# version2_PNP.net
KiCad netlist of a schematic drawn in EAGLE
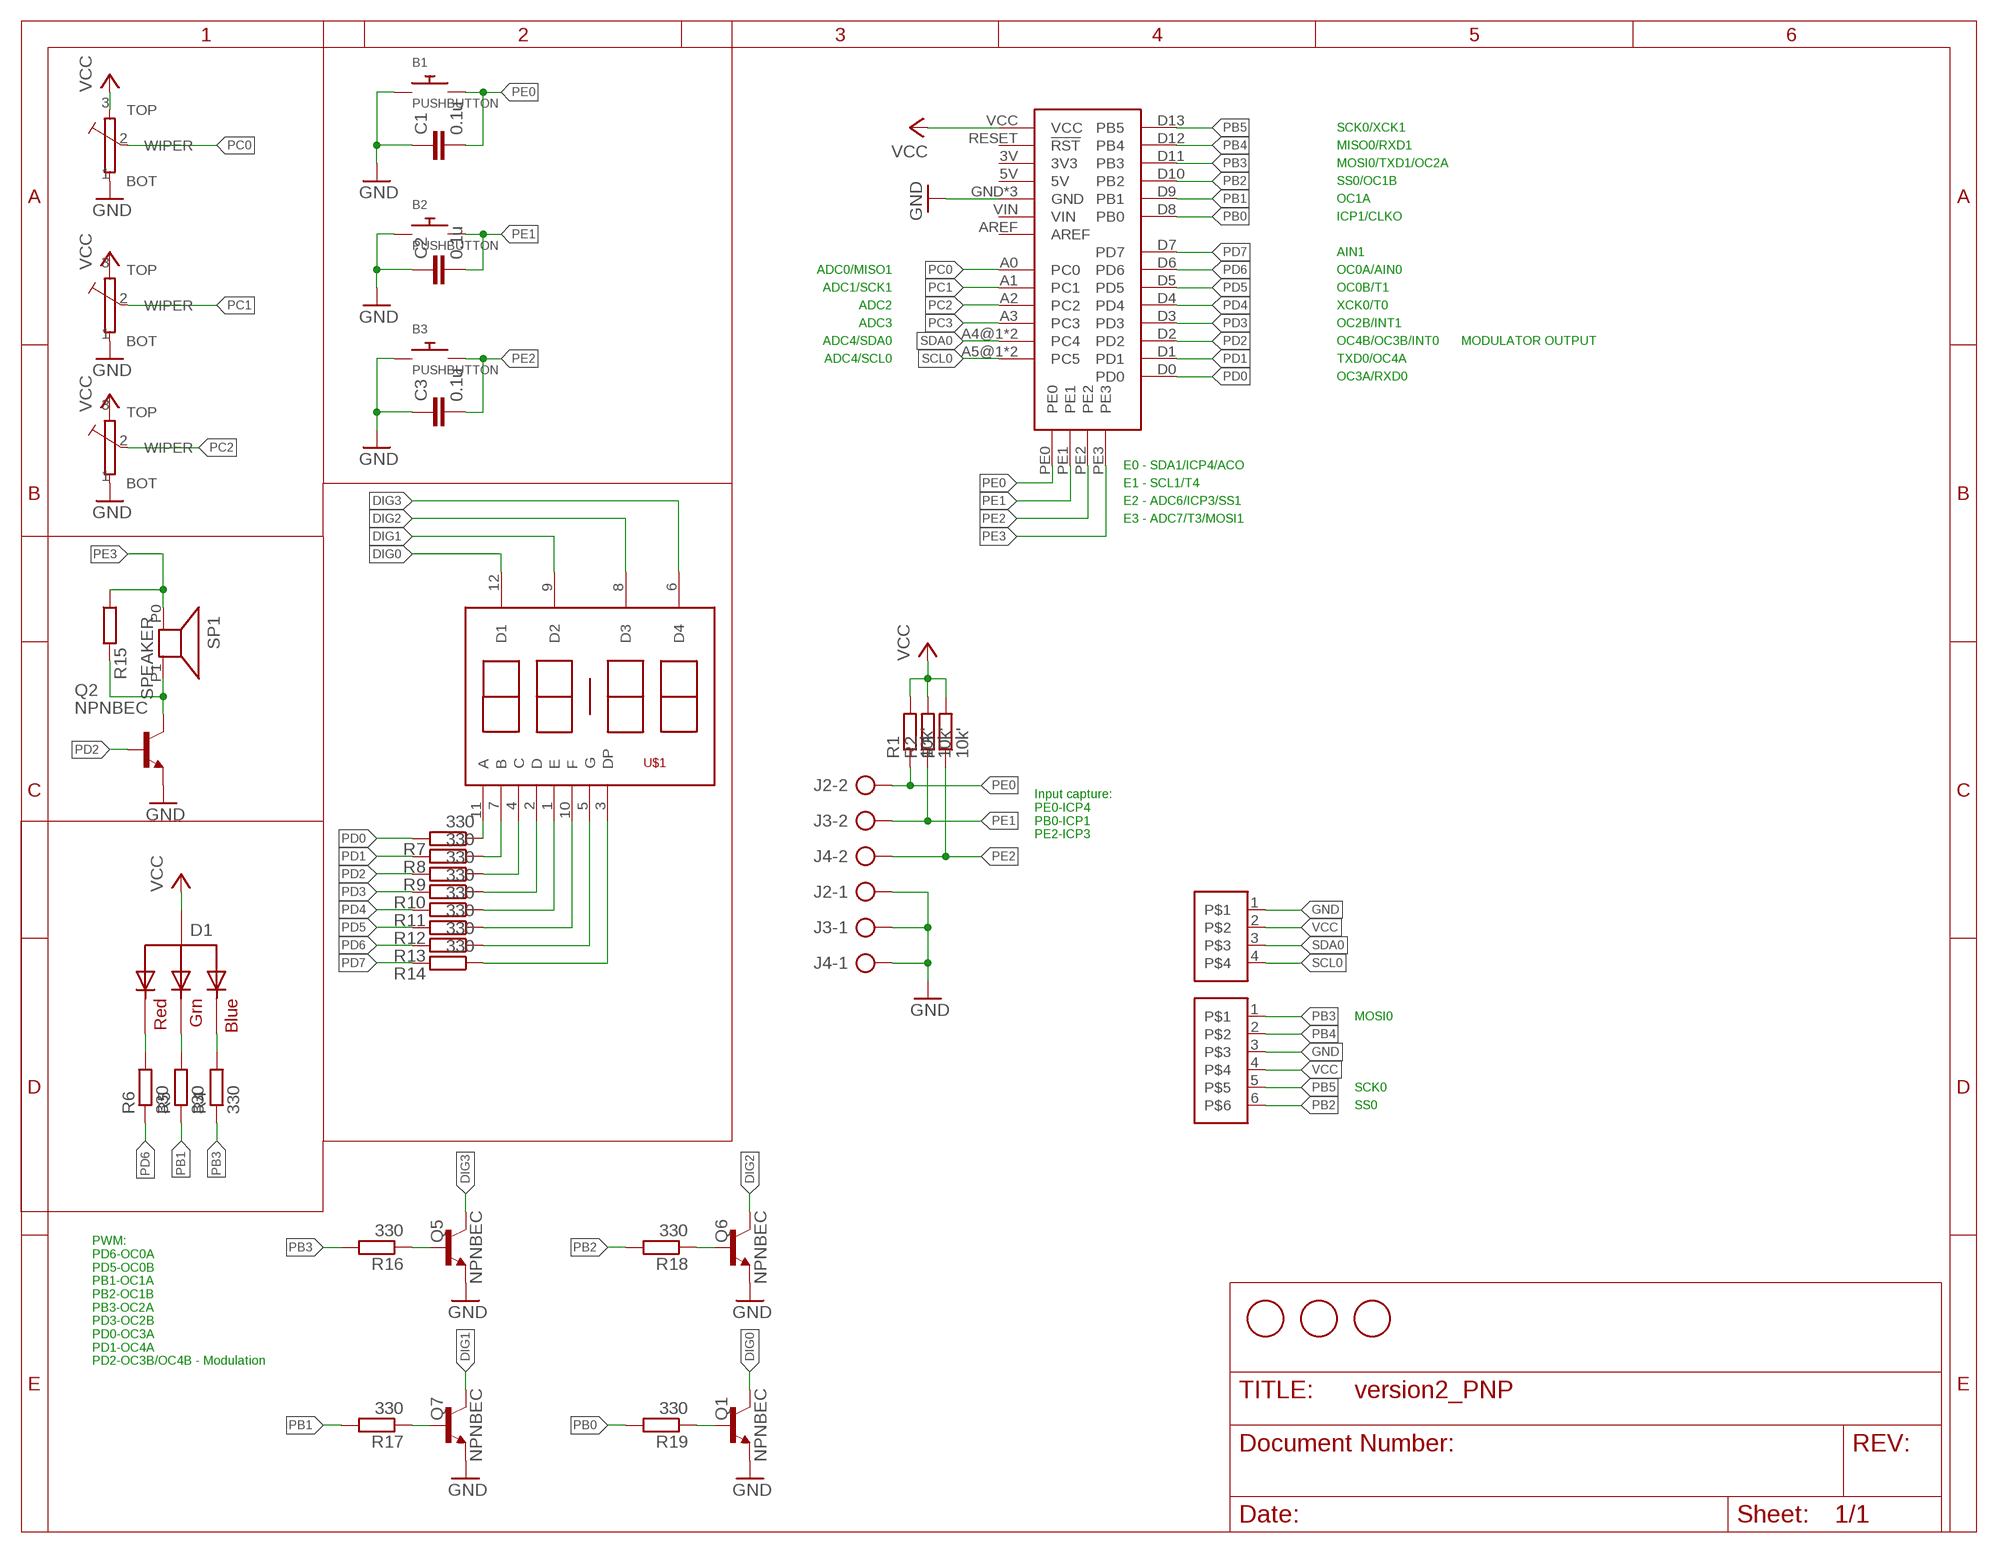
[diagram p0: schematic, sheet 1]

(export (version "E")
  (design (tool "Eeschema 10.0.6"))
  (components
    (comp (ref "B1")
      (value "PUSHBUTTON")
      (footprint "eagle-import:BUTTON_EVPBF")
      (libsource (lib "eagle-import") (part "PUSHBUTTON"))
    )
    (comp (ref "B2")
      (value "PUSHBUTTON")
      (footprint "eagle-import:BUTTON_EVPBF")
      (libsource (lib "eagle-import") (part "PUSHBUTTON"))
    )
    (comp (ref "B3")
      (value "PUSHBUTTON")
      (footprint "eagle-import:BUTTON_EVPBF")
      (libsource (lib "eagle-import") (part "PUSHBUTTON"))
    )
    (comp (ref "C1")
      (value "0.1u")
      (footprint "eagle-import:C0805")
      (libsource (lib "eagle-import") (part "C-EUC0805"))
    )
    (comp (ref "C2")
      (value "0.1u")
      (footprint "eagle-import:C0805")
      (libsource (lib "eagle-import") (part "C-EUC0805"))
    )
    (comp (ref "C3")
      (value "0.1u")
      (footprint "eagle-import:C0805")
      (libsource (lib "eagle-import") (part "C-EUC0805"))
    )
    (comp (ref "D1")
      (value "RGB_CA")
      (footprint "eagle-import:PLCC-4")
      (libsource (lib "eagle-import") (part "RGB_CA"))
    )
    (comp (ref "J1")
      (value "M04F")
      (footprint "eagle-import:1X04_FEMALE")
      (libsource (lib "eagle-import") (part "M04F"))
    )
    (comp (ref "J2")
      (value "1X02CLEAN")
      (footprint "eagle-import:1X02_CLEAN")
      (libsource (lib "eagle-import") (part "1X02CLEAN"))
    )
    (comp (ref "J3")
      (value "1X02CLEAN")
      (footprint "eagle-import:1X02_CLEAN")
      (libsource (lib "eagle-import") (part "1X02CLEAN"))
    )
    (comp (ref "J4")
      (value "1X02CLEAN")
      (footprint "eagle-import:1X02_CLEAN")
      (libsource (lib "eagle-import") (part "1X02CLEAN"))
    )
    (comp (ref "Q1")
      (value "NPNBEC")
      (footprint "eagle-import:SOT23")
      (libsource (lib "eagle-import") (part "NPNBEC"))
    )
    (comp (ref "Q2")
      (value "NPNBEC")
      (footprint "eagle-import:SOT23")
      (libsource (lib "eagle-import") (part "NPNBEC"))
    )
    (comp (ref "Q5")
      (value "NPNBEC")
      (footprint "eagle-import:SOT23")
      (libsource (lib "eagle-import") (part "NPNBEC"))
    )
    (comp (ref "Q6")
      (value "NPNBEC")
      (footprint "eagle-import:SOT23")
      (libsource (lib "eagle-import") (part "NPNBEC"))
    )
    (comp (ref "Q7")
      (value "NPNBEC")
      (footprint "eagle-import:SOT23")
      (libsource (lib "eagle-import") (part "NPNBEC"))
    )
    (comp (ref "R1")
      (value "10k'")
      (footprint "eagle-import:R0805")
      (libsource (lib "eagle-import") (part "R-EU_R0805"))
    )
    (comp (ref "R2")
      (value "10k'")
      (footprint "eagle-import:R0805")
      (libsource (lib "eagle-import") (part "R-EU_R0805"))
    )
    (comp (ref "R3")
      (value "10k'")
      (footprint "eagle-import:R0805")
      (libsource (lib "eagle-import") (part "R-EU_R0805"))
    )
    (comp (ref "R4")
      (value "330")
      (footprint "eagle-import:R0805")
      (libsource (lib "eagle-import") (part "R-EU_R0805"))
    )
    (comp (ref "R5")
      (value "330")
      (footprint "eagle-import:R0805")
      (libsource (lib "eagle-import") (part "R-EU_R0805"))
    )
    (comp (ref "R6")
      (value "330")
      (footprint "eagle-import:R0805")
      (libsource (lib "eagle-import") (part "R-EU_R0805"))
    )
    (comp (ref "R7")
      (value "330")
      (footprint "eagle-import:R0805")
      (libsource (lib "eagle-import") (part "R-EU_R0805"))
    )
    (comp (ref "R8")
      (value "330")
      (footprint "eagle-import:R0805")
      (libsource (lib "eagle-import") (part "R-EU_R0805"))
    )
    (comp (ref "R9")
      (value "330")
      (footprint "eagle-import:R0805")
      (libsource (lib "eagle-import") (part "R-EU_R0805"))
    )
    (comp (ref "R10")
      (value "330")
      (footprint "eagle-import:R0805")
      (libsource (lib "eagle-import") (part "R-EU_R0805"))
    )
    (comp (ref "R11")
      (value "330")
      (footprint "eagle-import:R0805")
      (libsource (lib "eagle-import") (part "R-EU_R0805"))
    )
    (comp (ref "R12")
      (value "330")
      (footprint "eagle-import:R0805")
      (libsource (lib "eagle-import") (part "R-EU_R0805"))
    )
    (comp (ref "R13")
      (value "330")
      (footprint "eagle-import:R0805")
      (libsource (lib "eagle-import") (part "R-EU_R0805"))
    )
    (comp (ref "R14")
      (value "330")
      (footprint "eagle-import:R0805")
      (libsource (lib "eagle-import") (part "R-EU_R0805"))
    )
    (comp (ref "R15")
      (value "R-EU_R0805")
      (footprint "eagle-import:R0805")
      (libsource (lib "eagle-import") (part "R-EU_R0805"))
    )
    (comp (ref "R16")
      (value "330")
      (footprint "eagle-import:R0805")
      (libsource (lib "eagle-import") (part "R-EU_R0805"))
    )
    (comp (ref "R17")
      (value "330")
      (footprint "eagle-import:R0805")
      (libsource (lib "eagle-import") (part "R-EU_R0805"))
    )
    (comp (ref "R18")
      (value "330")
      (footprint "eagle-import:R0805")
      (libsource (lib "eagle-import") (part "R-EU_R0805"))
    )
    (comp (ref "R19")
      (value "330")
      (footprint "eagle-import:R0805")
      (libsource (lib "eagle-import") (part "R-EU_R0805"))
    )
    (comp (ref "SP1")
      (value "SPEAKER")
      (footprint "eagle-import:PKMCS_SPEAKER")
      (libsource (lib "eagle-import") (part "SPEAKER"))
    )
    (comp (ref "TR1")
      (value "TRIMMTHUMB")
      (footprint "eagle-import:RV09")
      (libsource (lib "eagle-import") (part "TRIMMTHUMB"))
    )
    (comp (ref "TR2")
      (value "TRIMMTHUMB")
      (footprint "eagle-import:RV09")
      (libsource (lib "eagle-import") (part "TRIMMTHUMB"))
    )
    (comp (ref "TR3")
      (value "TRIMMTHUMB")
      (footprint "eagle-import:RV09")
      (libsource (lib "eagle-import") (part "TRIMMTHUMB"))
    )
    (comp (ref "U$1")
      (value "4DIG_7SEG_CATHODE")
      (footprint "eagle-import:4DIG_7SEG_CLOCK")
      (libsource (lib "eagle-import") (part "4DIG_7SEG_CATHODE"))
    )
    (comp (ref "U$2")
      (value "M06F")
      (footprint "eagle-import:1X06_FEMALE")
      (libsource (lib "eagle-import") (part "M06F"))
    )
    (comp (ref "U$3")
      (value "FIDUCIAL")
      (footprint "eagle-import:FIDUCIAL_1MM")
      (libsource (lib "eagle-import") (part "FIDUCIAL"))
    )
    (comp (ref "U$4")
      (value "FIDUCIAL")
      (footprint "eagle-import:FIDUCIAL_1MM")
      (libsource (lib "eagle-import") (part "FIDUCIAL"))
    )
    (comp (ref "U$5")
      (value "FIDUCIAL")
      (footprint "eagle-import:FIDUCIAL_1MM")
      (libsource (lib "eagle-import") (part "FIDUCIAL"))
    )
    (comp (ref "U2")
      (value "XPLAINEDMINI328PB")
      (footprint "eagle-import:XPLAINEDMINI328P")
      (libsource (lib "eagle-import") (part "XPLAINEDMINI328PB"))
    )
  )
  (nets
    (net (code "1") (name "DIG0") (class "Default")
      (node (ref "Q1") (pin "3") (pinfunction "C_3") (pintype "passive"))
      (node (ref "U$1") (pin "12") (pinfunction "D1_12") (pintype "bidirectional"))
    )
    (net (code "2") (name "DIG1") (class "Default")
      (node (ref "Q7") (pin "3") (pinfunction "C_3") (pintype "passive"))
      (node (ref "U$1") (pin "9") (pinfunction "D2_9") (pintype "bidirectional"))
    )
    (net (code "3") (name "DIG2") (class "Default")
      (node (ref "Q6") (pin "3") (pinfunction "C_3") (pintype "passive"))
      (node (ref "U$1") (pin "8") (pinfunction "D3_8") (pintype "bidirectional"))
    )
    (net (code "4") (name "DIG3") (class "Default")
      (node (ref "Q5") (pin "3") (pinfunction "C_3") (pintype "passive"))
      (node (ref "U$1") (pin "6") (pinfunction "D4_6") (pintype "bidirectional"))
    )
    (net (code "5") (name "GND") (class "Default")
      (node (ref "B1") (pin "A1") (pinfunction "P$1_A1") (pintype "passive"))
      (node (ref "B1") (pin "A2") (pinfunction "P$1_A2") (pintype "passive"))
      (node (ref "B2") (pin "A1") (pinfunction "P$1_A1") (pintype "passive"))
      (node (ref "B2") (pin "A2") (pinfunction "P$1_A2") (pintype "passive"))
      (node (ref "B3") (pin "A1") (pinfunction "P$1_A1") (pintype "passive"))
      (node (ref "B3") (pin "A2") (pinfunction "P$1_A2") (pintype "passive"))
      (node (ref "C1") (pin "1") (pinfunction "1_1") (pintype "passive"))
      (node (ref "C2") (pin "1") (pinfunction "1_1") (pintype "passive"))
      (node (ref "C3") (pin "1") (pinfunction "1_1") (pintype "passive"))
      (node (ref "J1") (pin "1") (pinfunction "P$1_1") (pintype "bidirectional"))
      (node (ref "J2") (pin "1") (pinfunction "KL_1") (pintype "passive"))
      (node (ref "J3") (pin "1") (pinfunction "KL_1") (pintype "passive"))
      (node (ref "J4") (pin "1") (pinfunction "KL_1") (pintype "passive"))
      (node (ref "Q1") (pin "2") (pinfunction "E_2") (pintype "passive"))
      (node (ref "Q2") (pin "2") (pinfunction "E_2") (pintype "passive"))
      (node (ref "Q5") (pin "2") (pinfunction "E_2") (pintype "passive"))
      (node (ref "Q6") (pin "2") (pinfunction "E_2") (pintype "passive"))
      (node (ref "Q7") (pin "2") (pinfunction "E_2") (pintype "passive"))
      (node (ref "TR1") (pin "1") (pinfunction "BOT_1") (pintype "bidirectional"))
      (node (ref "TR2") (pin "1") (pinfunction "BOT_1") (pintype "bidirectional"))
      (node (ref "TR3") (pin "1") (pinfunction "BOT_1") (pintype "bidirectional"))
      (node (ref "U$2") (pin "3") (pinfunction "P$3_3") (pintype "bidirectional"))
      (node (ref "U2") (pin "GND") (pinfunction "GND_GND") (pintype "bidirectional"))
      (node (ref "U2") (pin "GND1") (pinfunction "GND_GND1") (pintype "bidirectional"))
      (node (ref "U2") (pin "GND2") (pinfunction "GND_GND2") (pintype "bidirectional"))
    )
    (net (code "6") (name "Net-(D1-BLUE)") (class "Default")
      (node (ref "D1") (pin "P2") (pinfunction "BLUE_P2") (pintype "bidirectional"))
      (node (ref "R4") (pin "2") (pinfunction "2_2") (pintype "passive"))
    )
    (net (code "7") (name "Net-(D1-GREEN)") (class "Default")
      (node (ref "D1") (pin "P3") (pinfunction "GREEN_P3") (pintype "bidirectional"))
      (node (ref "R5") (pin "2") (pinfunction "2_2") (pintype "passive"))
    )
    (net (code "8") (name "Net-(D1-RED)") (class "Default")
      (node (ref "D1") (pin "P4") (pinfunction "RED_P4") (pintype "bidirectional"))
      (node (ref "R6") (pin "2") (pinfunction "2_2") (pintype "passive"))
    )
    (net (code "9") (name "Net-(Q1-B)") (class "Default")
      (node (ref "Q1") (pin "1") (pinfunction "B_1") (pintype "passive"))
      (node (ref "R19") (pin "1") (pinfunction "1_1") (pintype "passive"))
    )
    (net (code "10") (name "Net-(Q2-C)") (class "Default")
      (node (ref "Q2") (pin "3") (pinfunction "C_3") (pintype "passive"))
      (node (ref "R15") (pin "2") (pinfunction "2_2") (pintype "passive"))
      (node (ref "SP1") (pin "P1") (pinfunction "2_P1") (pintype "passive"))
    )
    (net (code "11") (name "Net-(Q5-B)") (class "Default")
      (node (ref "Q5") (pin "1") (pinfunction "B_1") (pintype "passive"))
      (node (ref "R16") (pin "1") (pinfunction "1_1") (pintype "passive"))
    )
    (net (code "12") (name "Net-(Q6-B)") (class "Default")
      (node (ref "Q6") (pin "1") (pinfunction "B_1") (pintype "passive"))
      (node (ref "R18") (pin "1") (pinfunction "1_1") (pintype "passive"))
    )
    (net (code "13") (name "Net-(Q7-B)") (class "Default")
      (node (ref "Q7") (pin "1") (pinfunction "B_1") (pintype "passive"))
      (node (ref "R17") (pin "1") (pinfunction "1_1") (pintype "passive"))
    )
    (net (code "14") (name "Net-(U$1-A)") (class "Default")
      (node (ref "R7") (pin "1") (pinfunction "1_1") (pintype "passive"))
      (node (ref "U$1") (pin "11") (pinfunction "A_11") (pintype "bidirectional"))
    )
    (net (code "15") (name "Net-(U$1-B)") (class "Default")
      (node (ref "R8") (pin "1") (pinfunction "1_1") (pintype "passive"))
      (node (ref "U$1") (pin "7") (pinfunction "B_7") (pintype "bidirectional"))
    )
    (net (code "16") (name "Net-(U$1-C)") (class "Default")
      (node (ref "R9") (pin "1") (pinfunction "1_1") (pintype "passive"))
      (node (ref "U$1") (pin "4") (pinfunction "C_4") (pintype "bidirectional"))
    )
    (net (code "17") (name "Net-(U$1-D)") (class "Default")
      (node (ref "R10") (pin "1") (pinfunction "1_1") (pintype "passive"))
      (node (ref "U$1") (pin "2") (pinfunction "D_2") (pintype "bidirectional"))
    )
    (net (code "18") (name "Net-(U$1-DP)") (class "Default")
      (node (ref "R14") (pin "1") (pinfunction "1_1") (pintype "passive"))
      (node (ref "U$1") (pin "3") (pinfunction "DP_3") (pintype "bidirectional"))
    )
    (net (code "19") (name "Net-(U$1-E)") (class "Default")
      (node (ref "R11") (pin "1") (pinfunction "1_1") (pintype "passive"))
      (node (ref "U$1") (pin "1") (pinfunction "E_1") (pintype "bidirectional"))
    )
    (net (code "20") (name "Net-(U$1-F)") (class "Default")
      (node (ref "R12") (pin "1") (pinfunction "1_1") (pintype "passive"))
      (node (ref "U$1") (pin "10") (pinfunction "F_10") (pintype "bidirectional"))
    )
    (net (code "21") (name "Net-(U$1-G)") (class "Default")
      (node (ref "R13") (pin "1") (pinfunction "1_1") (pintype "passive"))
      (node (ref "U$1") (pin "5") (pinfunction "G_5") (pintype "bidirectional"))
    )
    (net (code "22") (name "PB0") (class "Default")
      (node (ref "R19") (pin "2") (pinfunction "2_2") (pintype "passive"))
      (node (ref "U2") (pin "D8") (pinfunction "PB0_D8") (pintype "bidirectional"))
    )
    (net (code "23") (name "PB1") (class "Default")
      (node (ref "R17") (pin "2") (pinfunction "2_2") (pintype "passive"))
      (node (ref "R5") (pin "1") (pinfunction "1_1") (pintype "passive"))
      (node (ref "U2") (pin "D9") (pinfunction "PB1_D9") (pintype "bidirectional"))
    )
    (net (code "24") (name "PB2") (class "Default")
      (node (ref "R18") (pin "2") (pinfunction "2_2") (pintype "passive"))
      (node (ref "U$2") (pin "6") (pinfunction "P$6_6") (pintype "bidirectional"))
      (node (ref "U2") (pin "D10") (pinfunction "PB2_D10") (pintype "bidirectional"))
    )
    (net (code "25") (name "PB3") (class "Default")
      (node (ref "R16") (pin "2") (pinfunction "2_2") (pintype "passive"))
      (node (ref "R4") (pin "1") (pinfunction "1_1") (pintype "passive"))
      (node (ref "U$2") (pin "1") (pinfunction "P$1_1") (pintype "bidirectional"))
      (node (ref "U2") (pin "D11") (pinfunction "PB3_D11") (pintype "bidirectional"))
    )
    (net (code "26") (name "PB4") (class "Default")
      (node (ref "U$2") (pin "2") (pinfunction "P$2_2") (pintype "bidirectional"))
      (node (ref "U2") (pin "D12") (pinfunction "PB4_D12") (pintype "bidirectional"))
    )
    (net (code "27") (name "PB5") (class "Default")
      (node (ref "U$2") (pin "5") (pinfunction "P$5_5") (pintype "bidirectional"))
      (node (ref "U2") (pin "D13") (pinfunction "PB5_D13") (pintype "bidirectional"))
    )
    (net (code "28") (name "PC0") (class "Default")
      (node (ref "TR1") (pin "2") (pinfunction "WIPER_2") (pintype "bidirectional"))
      (node (ref "U2") (pin "A0") (pinfunction "PC0_A0") (pintype "bidirectional"))
    )
    (net (code "29") (name "PC1") (class "Default")
      (node (ref "TR2") (pin "2") (pinfunction "WIPER_2") (pintype "bidirectional"))
      (node (ref "U2") (pin "A1") (pinfunction "PC1_A1") (pintype "bidirectional"))
    )
    (net (code "30") (name "PC2") (class "Default")
      (node (ref "TR3") (pin "2") (pinfunction "WIPER_2") (pintype "bidirectional"))
      (node (ref "U2") (pin "A2") (pinfunction "PC2_A2") (pintype "bidirectional"))
    )
    (net (code "31") (name "PC3") (class "Default")
      (node (ref "U2") (pin "A3") (pinfunction "PC3_A3") (pintype "bidirectional"))
    )
    (net (code "32") (name "PD0") (class "Default")
      (node (ref "R7") (pin "2") (pinfunction "2_2") (pintype "passive"))
      (node (ref "U2") (pin "D0") (pinfunction "PD0_D0") (pintype "bidirectional"))
    )
    (net (code "33") (name "PD1") (class "Default")
      (node (ref "R8") (pin "2") (pinfunction "2_2") (pintype "passive"))
      (node (ref "U2") (pin "D1") (pinfunction "PD1_D1") (pintype "bidirectional"))
    )
    (net (code "34") (name "PD2") (class "Default")
      (node (ref "Q2") (pin "1") (pinfunction "B_1") (pintype "passive"))
      (node (ref "R9") (pin "2") (pinfunction "2_2") (pintype "passive"))
      (node (ref "U2") (pin "D2") (pinfunction "PD2_D2") (pintype "bidirectional"))
    )
    (net (code "35") (name "PD3") (class "Default")
      (node (ref "R10") (pin "2") (pinfunction "2_2") (pintype "passive"))
      (node (ref "U2") (pin "D3") (pinfunction "PD3_D3") (pintype "bidirectional"))
    )
    (net (code "36") (name "PD4") (class "Default")
      (node (ref "R11") (pin "2") (pinfunction "2_2") (pintype "passive"))
      (node (ref "U2") (pin "D4") (pinfunction "PD4_D4") (pintype "bidirectional"))
    )
    (net (code "37") (name "PD5") (class "Default")
      (node (ref "R12") (pin "2") (pinfunction "2_2") (pintype "passive"))
      (node (ref "U2") (pin "D5") (pinfunction "PD5_D5") (pintype "bidirectional"))
    )
    (net (code "38") (name "PD6") (class "Default")
      (node (ref "R13") (pin "2") (pinfunction "2_2") (pintype "passive"))
      (node (ref "R6") (pin "1") (pinfunction "1_1") (pintype "passive"))
      (node (ref "U2") (pin "D6") (pinfunction "PD6_D6") (pintype "bidirectional"))
    )
    (net (code "39") (name "PD7") (class "Default")
      (node (ref "R14") (pin "2") (pinfunction "2_2") (pintype "passive"))
      (node (ref "U2") (pin "D7") (pinfunction "PD7_D7") (pintype "bidirectional"))
    )
    (net (code "40") (name "PE0") (class "Default")
      (node (ref "B1") (pin "B1") (pinfunction "P$2_B1") (pintype "passive"))
      (node (ref "B1") (pin "B2") (pinfunction "P$2_B2") (pintype "passive"))
      (node (ref "C1") (pin "2") (pinfunction "2_2") (pintype "passive"))
      (node (ref "J2") (pin "2") (pinfunction "KL_2") (pintype "passive"))
      (node (ref "R1") (pin "1") (pinfunction "1_1") (pintype "passive"))
      (node (ref "U2") (pin "PE0") (pinfunction "PE0_PE0") (pintype "bidirectional"))
    )
    (net (code "41") (name "PE1") (class "Default")
      (node (ref "B2") (pin "B1") (pinfunction "P$2_B1") (pintype "passive"))
      (node (ref "B2") (pin "B2") (pinfunction "P$2_B2") (pintype "passive"))
      (node (ref "C2") (pin "2") (pinfunction "2_2") (pintype "passive"))
      (node (ref "J3") (pin "2") (pinfunction "KL_2") (pintype "passive"))
      (node (ref "R2") (pin "1") (pinfunction "1_1") (pintype "passive"))
      (node (ref "U2") (pin "PE1") (pinfunction "PE1_PE1") (pintype "bidirectional"))
    )
    (net (code "42") (name "PE2") (class "Default")
      (node (ref "B3") (pin "B1") (pinfunction "P$2_B1") (pintype "passive"))
      (node (ref "B3") (pin "B2") (pinfunction "P$2_B2") (pintype "passive"))
      (node (ref "C3") (pin "2") (pinfunction "2_2") (pintype "passive"))
      (node (ref "J4") (pin "2") (pinfunction "KL_2") (pintype "passive"))
      (node (ref "R3") (pin "1") (pinfunction "1_1") (pintype "passive"))
      (node (ref "U2") (pin "PE2") (pinfunction "PE2_PE2") (pintype "bidirectional"))
    )
    (net (code "43") (name "PE3") (class "Default")
      (node (ref "R15") (pin "1") (pinfunction "1_1") (pintype "passive"))
      (node (ref "SP1") (pin "P0") (pinfunction "1_P0") (pintype "passive"))
      (node (ref "U2") (pin "PE3") (pinfunction "PE3_PE3") (pintype "bidirectional"))
    )
    (net (code "44") (name "SCL0") (class "Default")
      (node (ref "J1") (pin "4") (pinfunction "P$4_4") (pintype "bidirectional"))
      (node (ref "U2") (pin "A5@1") (pinfunction "PC5_A5@1") (pintype "bidirectional"))
      (node (ref "U2") (pin "A5@2") (pinfunction "PC5_A5@2") (pintype "bidirectional"))
    )
    (net (code "45") (name "SDA0") (class "Default")
      (node (ref "J1") (pin "3") (pinfunction "P$3_3") (pintype "bidirectional"))
      (node (ref "U2") (pin "A4@1") (pinfunction "PC4_A4@1") (pintype "bidirectional"))
      (node (ref "U2") (pin "A4@2") (pinfunction "PC4_A4@2") (pintype "bidirectional"))
    )
    (net (code "46") (name "VCC") (class "Default")
      (node (ref "D1") (pin "P1") (pinfunction "VCC_P1") (pintype "bidirectional"))
      (node (ref "J1") (pin "2") (pinfunction "P$2_2") (pintype "bidirectional"))
      (node (ref "R1") (pin "2") (pinfunction "2_2") (pintype "passive"))
      (node (ref "R2") (pin "2") (pinfunction "2_2") (pintype "passive"))
      (node (ref "R3") (pin "2") (pinfunction "2_2") (pintype "passive"))
      (node (ref "TR1") (pin "3") (pinfunction "TOP_3") (pintype "bidirectional"))
      (node (ref "TR2") (pin "3") (pinfunction "TOP_3") (pintype "bidirectional"))
      (node (ref "TR3") (pin "3") (pinfunction "TOP_3") (pintype "bidirectional"))
      (node (ref "U$2") (pin "4") (pinfunction "P$4_4") (pintype "bidirectional"))
      (node (ref "U2") (pin "VCC") (pinfunction "VCC_VCC") (pintype "bidirectional"))
    )
    (net (code "47") (name "unconnected-(U2-3V3-Pad3V)") (class "Default")
      (node (ref "U2") (pin "3V") (pinfunction "3V3_3V") (pintype "bidirectional"))
    )
    (net (code "48") (name "unconnected-(U2-Pad5V)") (class "Default")
      (node (ref "U2") (pin "5V") (pinfunction "5V_5V") (pintype "bidirectional"))
    )
    (net (code "49") (name "unconnected-(U2-PadAREF)") (class "Default")
      (node (ref "U2") (pin "AREF") (pinfunction "AREF_AREF") (pintype "bidirectional"))
    )
    (net (code "50") (name "unconnected-(U2-PadVIN)") (class "Default")
      (node (ref "U2") (pin "VIN") (pinfunction "VIN_VIN") (pintype "bidirectional"))
    )
    (net (code "51") (name "unconnected-(U2-~{RST}-PadRESET)") (class "Default")
      (node (ref "U2") (pin "RESET") (pinfunction "~{RST}_RESET") (pintype "bidirectional"))
    )
  )
)
